# OpenSoundPhoton.net
KiCad netlist of a schematic drawn in EAGLE
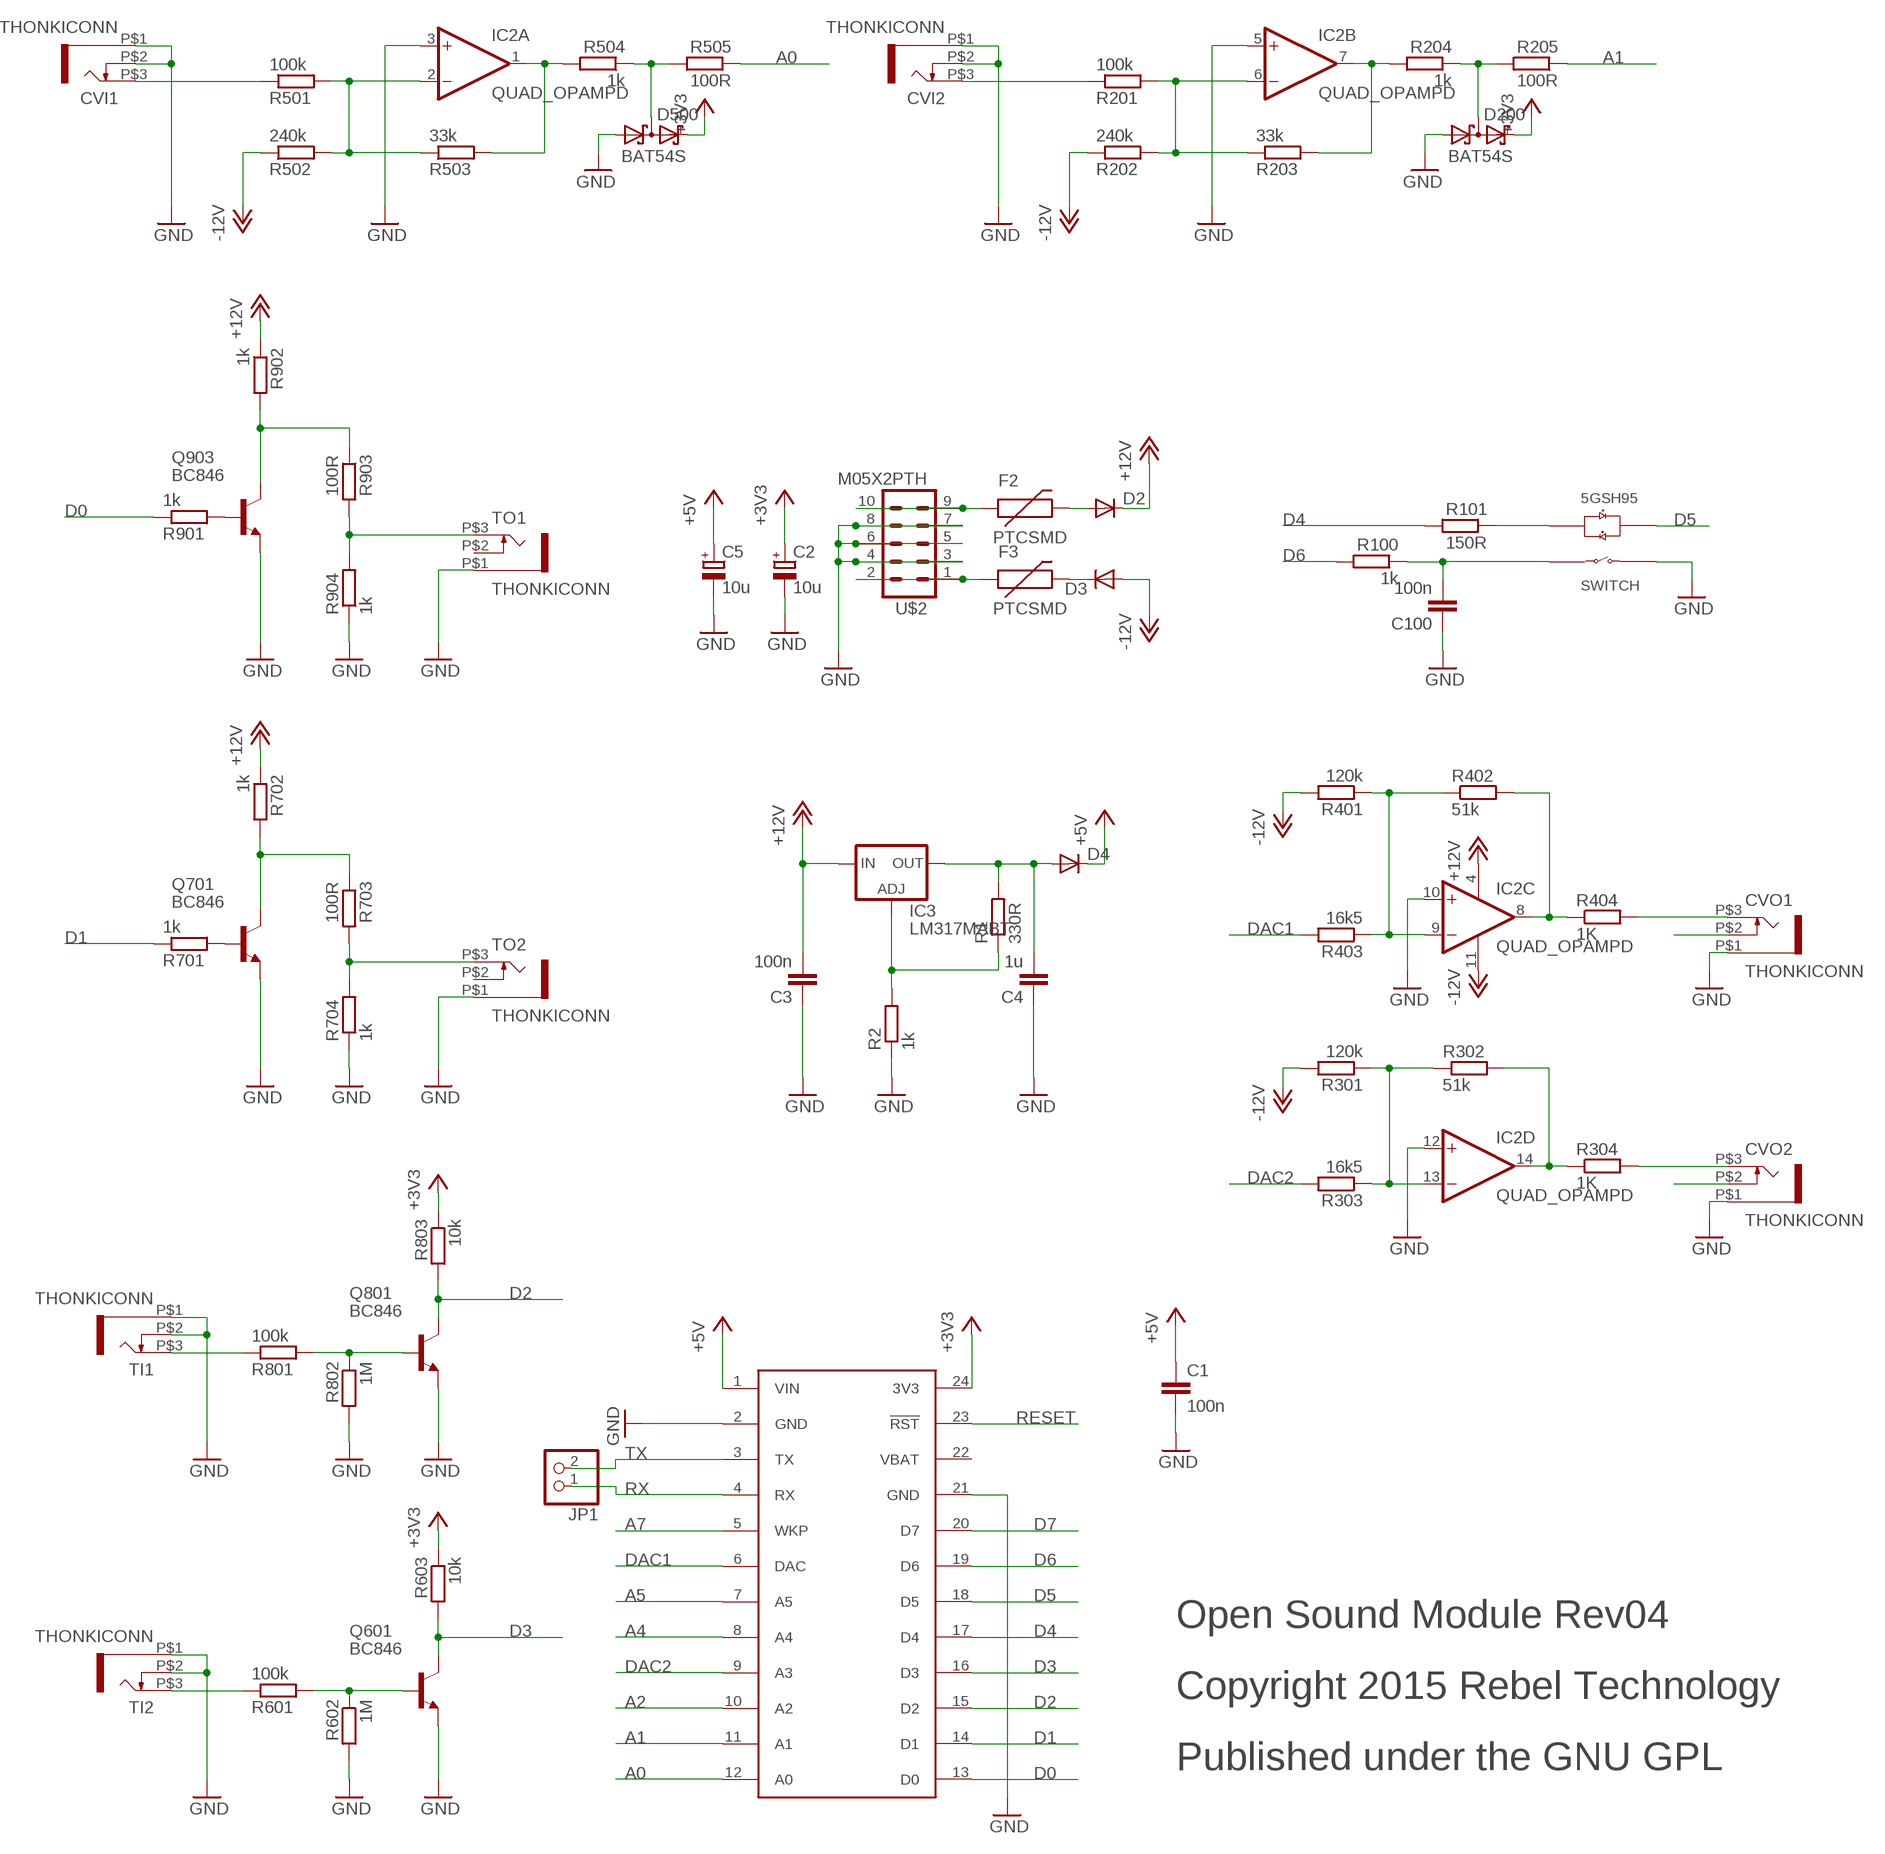
[diagram p0: schematic, sheet 1]

(export (version "E")
  (design (tool "Eeschema 10.0.6"))
  (components
    (comp (ref "C1")
      (value "100n")
      (footprint "eagle-import:C0603")
      (libsource (lib "eagle-import") (part "resistor_C-EUC0603"))
    )
    (comp (ref "C2")
      (value "10u")
      (footprint "eagle-import:SANYO-OSCON_SMD_A5")
      (libsource (lib "eagle-import") (part "CPOL-EUSANYO_SMD_A5"))
    )
    (comp (ref "C3")
      (value "100n")
      (footprint "eagle-import:C0603")
      (libsource (lib "eagle-import") (part "C-EUC0603"))
    )
    (comp (ref "C4")
      (value "1u")
      (footprint "eagle-import:C0603")
      (libsource (lib "eagle-import") (part "C-EUC0603"))
    )
    (comp (ref "C5")
      (value "10u")
      (footprint "eagle-import:SANYO-OSCON_SMD_A5")
      (libsource (lib "eagle-import") (part "CPOL-EUSANYO_SMD_A5"))
    )
    (comp (ref "C100")
      (value "100n")
      (footprint "eagle-import:C0603")
      (libsource (lib "eagle-import") (part "C-EUC0603"))
    )
    (comp (ref "CVI1")
      (value "THONKICONN")
      (footprint "eagle-import:THONKICONN")
      (libsource (lib "eagle-import") (part "THONKICONN"))
    )
    (comp (ref "CVI2")
      (value "THONKICONN")
      (footprint "eagle-import:THONKICONN")
      (libsource (lib "eagle-import") (part "THONKICONN"))
    )
    (comp (ref "CVO1")
      (value "THONKICONN")
      (footprint "eagle-import:THONKICONN")
      (libsource (lib "eagle-import") (part "THONKICONN"))
    )
    (comp (ref "CVO2")
      (value "THONKICONN")
      (footprint "eagle-import:THONKICONN")
      (libsource (lib "eagle-import") (part "THONKICONN"))
    )
    (comp (ref "D2")
      (value "DIODESMA")
      (footprint "eagle-import:SMA-DIODE")
      (libsource (lib "eagle-import") (part "DIODESMA"))
    )
    (comp (ref "D3")
      (value "DIODESMA")
      (footprint "eagle-import:SMA-DIODE")
      (libsource (lib "eagle-import") (part "DIODESMA"))
    )
    (comp (ref "D4")
      (value "DIODESMA")
      (footprint "eagle-import:SMA-DIODE")
      (libsource (lib "eagle-import") (part "DIODESMA"))
    )
    (comp (ref "D200")
      (value "BAT54S")
      (footprint "eagle-import:SOT23")
      (libsource (lib "eagle-import") (part "BAT54S"))
    )
    (comp (ref "D500")
      (value "BAT54S")
      (footprint "eagle-import:SOT23")
      (libsource (lib "eagle-import") (part "BAT54S"))
    )
    (comp (ref "F2")
      (value "PTCSMD")
      (footprint "eagle-import:PTC-1206")
      (libsource (lib "eagle-import") (part "PTCSMD"))
    )
    (comp (ref "F3")
      (value "PTCSMD")
      (footprint "eagle-import:PTC-1206")
      (libsource (lib "eagle-import") (part "PTCSMD"))
    )
    (comp (ref "IC2")
      (value "QUAD_OPAMPD")
      (footprint "eagle-import:SO14")
      (libsource (lib "eagle-import") (part "QUAD_OPAMPD"))
    )
    (comp (ref "IC3")
      (value "LM317MABT")
      (footprint "eagle-import:TO220L1")
      (libsource (lib "eagle-import") (part "LM317?MABT"))
    )
    (comp (ref "JP1")
      (value "PINHD-1X2")
      (footprint "eagle-import:1X02")
      (libsource (lib "eagle-import") (part "PINHD-1X2"))
    )
    (comp (ref "Q601")
      (value "BC846")
      (footprint "eagle-import:SOT23")
      (libsource (lib "eagle-import") (part "BC846"))
    )
    (comp (ref "Q701")
      (value "BC846")
      (footprint "eagle-import:SOT23")
      (libsource (lib "eagle-import") (part "BC846"))
    )
    (comp (ref "Q801")
      (value "BC846")
      (footprint "eagle-import:SOT23")
      (libsource (lib "eagle-import") (part "BC846"))
    )
    (comp (ref "Q903")
      (value "BC846")
      (footprint "eagle-import:SOT23")
      (libsource (lib "eagle-import") (part "BC846"))
    )
    (comp (ref "R1")
      (value "330R")
      (footprint "eagle-import:0603")
      (libsource (lib "eagle-import") (part "R-EU_0603"))
    )
    (comp (ref "R2")
      (value "1k")
      (footprint "eagle-import:0603")
      (libsource (lib "eagle-import") (part "R-EU_0603"))
    )
    (comp (ref "R100")
      (value "1k")
      (footprint "eagle-import:0603")
      (libsource (lib "eagle-import") (part "R-EU_0603"))
    )
    (comp (ref "R101")
      (value "150R")
      (footprint "eagle-import:0603")
      (libsource (lib "eagle-import") (part "R-EU_0603"))
    )
    (comp (ref "R201")
      (value "100k")
      (footprint "eagle-import:0603")
      (libsource (lib "eagle-import") (part "R-EU_0603"))
    )
    (comp (ref "R202")
      (value "240k")
      (footprint "eagle-import:0603")
      (libsource (lib "eagle-import") (part "R-EU_0603"))
    )
    (comp (ref "R203")
      (value "33k")
      (footprint "eagle-import:0603")
      (libsource (lib "eagle-import") (part "R-EU_0603"))
    )
    (comp (ref "R204")
      (value "1k")
      (footprint "eagle-import:0603")
      (libsource (lib "eagle-import") (part "R-EU_0603"))
    )
    (comp (ref "R205")
      (value "100R")
      (footprint "eagle-import:0603")
      (libsource (lib "eagle-import") (part "R-EU_0603"))
    )
    (comp (ref "R301")
      (value "120k")
      (footprint "eagle-import:0603")
      (libsource (lib "eagle-import") (part "R-EU_0603"))
    )
    (comp (ref "R302")
      (value "51k")
      (footprint "eagle-import:0603")
      (libsource (lib "eagle-import") (part "R-EU_0603"))
    )
    (comp (ref "R303")
      (value "16k5")
      (footprint "eagle-import:0603")
      (libsource (lib "eagle-import") (part "R-EU_0603"))
    )
    (comp (ref "R304")
      (value "1K")
      (footprint "eagle-import:0603")
      (libsource (lib "eagle-import") (part "R-EU_0603"))
    )
    (comp (ref "R401")
      (value "120k")
      (footprint "eagle-import:0603")
      (libsource (lib "eagle-import") (part "R-EU_0603"))
    )
    (comp (ref "R402")
      (value "51k")
      (footprint "eagle-import:0603")
      (libsource (lib "eagle-import") (part "R-EU_0603"))
    )
    (comp (ref "R403")
      (value "16k5")
      (footprint "eagle-import:0603")
      (libsource (lib "eagle-import") (part "R-EU_0603"))
    )
    (comp (ref "R404")
      (value "1K")
      (footprint "eagle-import:0603")
      (libsource (lib "eagle-import") (part "R-EU_0603"))
    )
    (comp (ref "R501")
      (value "100k")
      (footprint "eagle-import:0603")
      (libsource (lib "eagle-import") (part "R-EU_0603"))
    )
    (comp (ref "R502")
      (value "240k")
      (footprint "eagle-import:0603")
      (libsource (lib "eagle-import") (part "R-EU_0603"))
    )
    (comp (ref "R503")
      (value "33k")
      (footprint "eagle-import:0603")
      (libsource (lib "eagle-import") (part "R-EU_0603"))
    )
    (comp (ref "R504")
      (value "1k")
      (footprint "eagle-import:0603")
      (libsource (lib "eagle-import") (part "R-EU_0603"))
    )
    (comp (ref "R505")
      (value "100R")
      (footprint "eagle-import:0603")
      (libsource (lib "eagle-import") (part "R-EU_0603"))
    )
    (comp (ref "R601")
      (value "100k")
      (footprint "eagle-import:0603")
      (libsource (lib "eagle-import") (part "R-EU_0603"))
    )
    (comp (ref "R602")
      (value "1M")
      (footprint "eagle-import:0603")
      (libsource (lib "eagle-import") (part "R-EU_0603"))
    )
    (comp (ref "R603")
      (value "10k")
      (footprint "eagle-import:0603")
      (libsource (lib "eagle-import") (part "R-EU_0603"))
    )
    (comp (ref "R701")
      (value "1k")
      (footprint "eagle-import:0603")
      (libsource (lib "eagle-import") (part "R-EU_0603"))
    )
    (comp (ref "R702")
      (value "1k")
      (footprint "eagle-import:0603")
      (libsource (lib "eagle-import") (part "R-EU_0603"))
    )
    (comp (ref "R703")
      (value "100R")
      (footprint "eagle-import:0603")
      (libsource (lib "eagle-import") (part "R-EU_0603"))
    )
    (comp (ref "R704")
      (value "1k")
      (footprint "eagle-import:0603")
      (libsource (lib "eagle-import") (part "R-EU_0603"))
    )
    (comp (ref "R801")
      (value "100k")
      (footprint "eagle-import:0603")
      (libsource (lib "eagle-import") (part "R-EU_0603"))
    )
    (comp (ref "R802")
      (value "1M")
      (footprint "eagle-import:0603")
      (libsource (lib "eagle-import") (part "R-EU_0603"))
    )
    (comp (ref "R803")
      (value "10k")
      (footprint "eagle-import:0603")
      (libsource (lib "eagle-import") (part "R-EU_0603"))
    )
    (comp (ref "R901")
      (value "1k")
      (footprint "eagle-import:0603")
      (libsource (lib "eagle-import") (part "R-EU_0603"))
    )
    (comp (ref "R902")
      (value "1k")
      (footprint "eagle-import:0603")
      (libsource (lib "eagle-import") (part "R-EU_0603"))
    )
    (comp (ref "R903")
      (value "100R")
      (footprint "eagle-import:0603")
      (libsource (lib "eagle-import") (part "R-EU_0603"))
    )
    (comp (ref "R904")
      (value "1k")
      (footprint "eagle-import:0603")
      (libsource (lib "eagle-import") (part "R-EU_0603"))
    )
    (comp (ref "SPARK")
      (value "SPARK_CORE")
      (footprint "eagle-import:SPARK_CORE")
      (libsource (lib "eagle-import") (part "SPARK_CORECORE"))
    )
    (comp (ref "TI1")
      (value "THONKICONN")
      (footprint "eagle-import:THONKICONN")
      (libsource (lib "eagle-import") (part "THONKICONN"))
    )
    (comp (ref "TI2")
      (value "THONKICONN")
      (footprint "eagle-import:THONKICONN")
      (libsource (lib "eagle-import") (part "THONKICONN"))
    )
    (comp (ref "TO1")
      (value "THONKICONN")
      (footprint "eagle-import:THONKICONN")
      (libsource (lib "eagle-import") (part "THONKICONN"))
    )
    (comp (ref "TO2")
      (value "THONKICONN")
      (footprint "eagle-import:THONKICONN")
      (libsource (lib "eagle-import") (part "THONKICONN"))
    )
    (comp (ref "U$1")
      (value "5GTH9")
      (footprint "eagle-import:5GTH9")
      (libsource (lib "eagle-import") (part "5GTH9"))
    )
    (comp (ref "U$2")
      (value "M05X2PTH")
      (footprint "eagle-import:AVR_ICSP")
      (libsource (lib "eagle-import") (part "M05X2PTH"))
    )
  )
  (nets
    (net (code "1") (name "+3V3") (class "Default")
      (node (ref "C2") (pin "+") (pinfunction "+_+") (pintype "passive"))
      (node (ref "D200") (pin "2") (pinfunction "C2_2") (pintype "passive"))
      (node (ref "D500") (pin "2") (pinfunction "C2_2") (pintype "passive"))
      (node (ref "R603") (pin "1") (pinfunction "1_1") (pintype "passive"))
      (node (ref "R803") (pin "1") (pinfunction "1_1") (pintype "passive"))
      (node (ref "SPARK") (pin "24") (pinfunction "3V3_24") (pintype "power_in"))
    )
    (net (code "2") (name "+5V") (class "Default")
      (node (ref "C1") (pin "1") (pinfunction "1_1") (pintype "passive"))
      (node (ref "C5") (pin "+") (pinfunction "+_+") (pintype "passive"))
      (node (ref "D4") (pin "C") (pinfunction "C_C") (pintype "passive"))
      (node (ref "SPARK") (pin "1") (pinfunction "VIN_1") (pintype "power_in"))
    )
    (net (code "3") (name "+12V") (class "Default")
      (node (ref "C3") (pin "2") (pinfunction "2_2") (pintype "passive"))
      (node (ref "D2") (pin "C") (pinfunction "C_C") (pintype "passive"))
      (node (ref "IC2") (pin "4") (pinfunction "V+_4") (pintype "power_in"))
      (node (ref "IC3") (pin "3") (pinfunction "IN_3") (pintype "input"))
      (node (ref "R702") (pin "1") (pinfunction "1_1") (pintype "passive"))
      (node (ref "R902") (pin "1") (pinfunction "1_1") (pintype "passive"))
    )
    (net (code "4") (name "-12V") (class "Default")
      (node (ref "D3") (pin "A") (pinfunction "A_A") (pintype "passive"))
      (node (ref "IC2") (pin "11") (pinfunction "V-_11") (pintype "power_in"))
      (node (ref "R202") (pin "1") (pinfunction "1_1") (pintype "passive"))
      (node (ref "R301") (pin "2") (pinfunction "2_2") (pintype "passive"))
      (node (ref "R401") (pin "2") (pinfunction "2_2") (pintype "passive"))
      (node (ref "R502") (pin "1") (pinfunction "1_1") (pintype "passive"))
    )
    (net (code "5") (name "/A0") (class "Default")
      (node (ref "R505") (pin "1") (pinfunction "1_1") (pintype "passive"))
      (node (ref "SPARK") (pin "12") (pinfunction "A0_12") (pintype "bidirectional"))
    )
    (net (code "6") (name "/A1") (class "Default")
      (node (ref "R205") (pin "1") (pinfunction "1_1") (pintype "passive"))
      (node (ref "SPARK") (pin "11") (pinfunction "A1_11") (pintype "bidirectional"))
    )
    (net (code "7") (name "/A2") (class "Default")
      (node (ref "SPARK") (pin "10") (pinfunction "A2_10") (pintype "bidirectional"))
    )
    (net (code "8") (name "/A4") (class "Default")
      (node (ref "SPARK") (pin "8") (pinfunction "A4_8") (pintype "bidirectional"))
    )
    (net (code "9") (name "/A5") (class "Default")
      (node (ref "SPARK") (pin "7") (pinfunction "A5_7") (pintype "bidirectional"))
    )
    (net (code "10") (name "/A7") (class "Default")
      (node (ref "SPARK") (pin "5") (pinfunction "WKP_5") (pintype "bidirectional"))
    )
    (net (code "11") (name "/D0") (class "Default")
      (node (ref "R901") (pin "1") (pinfunction "1_1") (pintype "passive"))
      (node (ref "SPARK") (pin "13") (pinfunction "D0_13") (pintype "bidirectional"))
    )
    (net (code "12") (name "/D1") (class "Default")
      (node (ref "R701") (pin "1") (pinfunction "1_1") (pintype "passive"))
      (node (ref "SPARK") (pin "14") (pinfunction "D1_14") (pintype "bidirectional"))
    )
    (net (code "13") (name "/D2") (class "Default")
      (node (ref "Q801") (pin "3") (pinfunction "C_3") (pintype "passive"))
      (node (ref "R803") (pin "2") (pinfunction "2_2") (pintype "passive"))
      (node (ref "SPARK") (pin "15") (pinfunction "D2_15") (pintype "bidirectional"))
    )
    (net (code "14") (name "/D3") (class "Default")
      (node (ref "Q601") (pin "3") (pinfunction "C_3") (pintype "passive"))
      (node (ref "R603") (pin "2") (pinfunction "2_2") (pintype "passive"))
      (node (ref "SPARK") (pin "16") (pinfunction "D3_16") (pintype "bidirectional"))
    )
    (net (code "15") (name "/D4") (class "Default")
      (node (ref "R101") (pin "2") (pinfunction "2_2") (pintype "passive"))
      (node (ref "SPARK") (pin "17") (pinfunction "D4_17") (pintype "bidirectional"))
    )
    (net (code "16") (name "/D5") (class "Default")
      (node (ref "SPARK") (pin "18") (pinfunction "D5_18") (pintype "bidirectional"))
      (node (ref "U$1") (pin "+3") (pinfunction "LED_R+_+3") (pintype "input"))
    )
    (net (code "17") (name "/D6") (class "Default")
      (node (ref "R100") (pin "2") (pinfunction "2_2") (pintype "passive"))
      (node (ref "SPARK") (pin "19") (pinfunction "D6_19") (pintype "bidirectional"))
    )
    (net (code "18") (name "/D7") (class "Default")
      (node (ref "SPARK") (pin "20") (pinfunction "D7_20") (pintype "bidirectional"))
    )
    (net (code "19") (name "/DAC1") (class "Default")
      (node (ref "R403") (pin "2") (pinfunction "2_2") (pintype "passive"))
      (node (ref "SPARK") (pin "6") (pinfunction "DAC_6") (pintype "bidirectional"))
    )
    (net (code "20") (name "/DAC2") (class "Default")
      (node (ref "R303") (pin "2") (pinfunction "2_2") (pintype "passive"))
      (node (ref "SPARK") (pin "9") (pinfunction "A3_9") (pintype "bidirectional"))
    )
    (net (code "21") (name "/RESET") (class "Default")
      (node (ref "SPARK") (pin "23") (pinfunction "~{RST}_23") (pintype "bidirectional"))
    )
    (net (code "22") (name "/RX") (class "Default")
      (node (ref "JP1") (pin "1") (pinfunction "1_1") (pintype "passive"))
      (node (ref "SPARK") (pin "4") (pinfunction "RX_4") (pintype "bidirectional"))
    )
    (net (code "23") (name "/TX") (class "Default")
      (node (ref "JP1") (pin "2") (pinfunction "2_2") (pintype "passive"))
      (node (ref "SPARK") (pin "3") (pinfunction "TX_3") (pintype "bidirectional"))
    )
    (net (code "24") (name "/VBAT") (class "Default")
      (node (ref "SPARK") (pin "22") (pinfunction "VBAT_22") (pintype "power_in"))
    )
    (net (code "25") (name "GND") (class "Default")
      (node (ref "C1") (pin "2") (pinfunction "2_2") (pintype "passive"))
      (node (ref "C100") (pin "1") (pinfunction "1_1") (pintype "passive"))
      (node (ref "C2") (pin "-") (pinfunction "-_-") (pintype "passive"))
      (node (ref "C3") (pin "1") (pinfunction "1_1") (pintype "passive"))
      (node (ref "C4") (pin "1") (pinfunction "1_1") (pintype "passive"))
      (node (ref "C5") (pin "-") (pinfunction "-_-") (pintype "passive"))
      (node (ref "CVI1") (pin "P$1") (pinfunction "5_P$1") (pintype "passive"))
      (node (ref "CVI1") (pin "P$2") (pinfunction "4_P$2") (pintype "passive"))
      (node (ref "CVI2") (pin "P$1") (pinfunction "5_P$1") (pintype "passive"))
      (node (ref "CVI2") (pin "P$2") (pinfunction "4_P$2") (pintype "passive"))
      (node (ref "CVO1") (pin "P$1") (pinfunction "5_P$1") (pintype "passive"))
      (node (ref "CVO2") (pin "P$1") (pinfunction "5_P$1") (pintype "passive"))
      (node (ref "D200") (pin "1") (pinfunction "A1_1") (pintype "passive"))
      (node (ref "D500") (pin "1") (pinfunction "A1_1") (pintype "passive"))
      (node (ref "IC2") (pin "10") (pinfunction "+IN_10") (pintype "input"))
      (node (ref "IC2") (pin "12") (pinfunction "+IN_12") (pintype "input"))
      (node (ref "IC2") (pin "3") (pinfunction "+IN_3") (pintype "input"))
      (node (ref "IC2") (pin "5") (pinfunction "+IN_5") (pintype "input"))
      (node (ref "Q601") (pin "2") (pinfunction "E_2") (pintype "passive"))
      (node (ref "Q701") (pin "2") (pinfunction "E_2") (pintype "passive"))
      (node (ref "Q801") (pin "2") (pinfunction "E_2") (pintype "passive"))
      (node (ref "Q903") (pin "2") (pinfunction "E_2") (pintype "passive"))
      (node (ref "R2") (pin "1") (pinfunction "1_1") (pintype "passive"))
      (node (ref "R602") (pin "2") (pinfunction "2_2") (pintype "passive"))
      (node (ref "R704") (pin "1") (pinfunction "1_1") (pintype "passive"))
      (node (ref "R802") (pin "2") (pinfunction "2_2") (pintype "passive"))
      (node (ref "R904") (pin "1") (pinfunction "1_1") (pintype "passive"))
      (node (ref "SPARK") (pin "2") (pinfunction "GND_2") (pintype "power_in"))
      (node (ref "SPARK") (pin "21") (pinfunction "GND_21") (pintype "power_in"))
      (node (ref "TI1") (pin "P$1") (pinfunction "5_P$1") (pintype "passive"))
      (node (ref "TI1") (pin "P$2") (pinfunction "4_P$2") (pintype "passive"))
      (node (ref "TI2") (pin "P$1") (pinfunction "5_P$1") (pintype "passive"))
      (node (ref "TI2") (pin "P$2") (pinfunction "4_P$2") (pintype "passive"))
      (node (ref "TO1") (pin "P$1") (pinfunction "5_P$1") (pintype "passive"))
      (node (ref "TO2") (pin "P$1") (pinfunction "5_P$1") (pintype "passive"))
      (node (ref "U$1") (pin "1") (pinfunction "SWITCH_B_1") (pintype "power_in"))
      (node (ref "U$2") (pin "3") (pinfunction "3_3") (pintype "passive"))
      (node (ref "U$2") (pin "4") (pinfunction "4_4") (pintype "passive"))
      (node (ref "U$2") (pin "5") (pinfunction "5_5") (pintype "passive"))
      (node (ref "U$2") (pin "6") (pinfunction "6_6") (pintype "passive"))
      (node (ref "U$2") (pin "7") (pinfunction "7_7") (pintype "passive"))
      (node (ref "U$2") (pin "8") (pinfunction "8_8") (pintype "passive"))
    )
    (net (code "26") (name "Net-(CVI1-3)") (class "Default")
      (node (ref "CVI1") (pin "P$3") (pinfunction "3_P$3") (pintype "passive"))
      (node (ref "R501") (pin "1") (pinfunction "1_1") (pintype "passive"))
    )
    (net (code "27") (name "Net-(CVI2-3)") (class "Default")
      (node (ref "CVI2") (pin "P$3") (pinfunction "3_P$3") (pintype "passive"))
      (node (ref "R201") (pin "1") (pinfunction "1_1") (pintype "passive"))
    )
    (net (code "28") (name "Net-(CVO1-3)") (class "Default")
      (node (ref "CVO1") (pin "P$3") (pinfunction "3_P$3") (pintype "passive"))
      (node (ref "R404") (pin "2") (pinfunction "2_2") (pintype "passive"))
    )
    (net (code "29") (name "Net-(CVO2-3)") (class "Default")
      (node (ref "CVO2") (pin "P$3") (pinfunction "3_P$3") (pintype "passive"))
      (node (ref "R304") (pin "2") (pinfunction "2_2") (pintype "passive"))
    )
    (net (code "30") (name "Net-(D2-PadA)") (class "Default")
      (node (ref "D2") (pin "A") (pinfunction "A_A") (pintype "passive"))
      (node (ref "F2") (pin "2") (pinfunction "2_2") (pintype "bidirectional"))
    )
    (net (code "31") (name "Net-(D3-PadC)") (class "Default")
      (node (ref "D3") (pin "C") (pinfunction "C_C") (pintype "passive"))
      (node (ref "F3") (pin "2") (pinfunction "2_2") (pintype "bidirectional"))
    )
    (net (code "32") (name "Net-(D200-C1A2)") (class "Default")
      (node (ref "D200") (pin "3") (pinfunction "C1A2_3") (pintype "passive"))
      (node (ref "R204") (pin "1") (pinfunction "1_1") (pintype "passive"))
      (node (ref "R205") (pin "2") (pinfunction "2_2") (pintype "passive"))
    )
    (net (code "33") (name "Net-(D500-C1A2)") (class "Default")
      (node (ref "D500") (pin "3") (pinfunction "C1A2_3") (pintype "passive"))
      (node (ref "R504") (pin "1") (pinfunction "1_1") (pintype "passive"))
      (node (ref "R505") (pin "2") (pinfunction "2_2") (pintype "passive"))
    )
    (net (code "34") (name "Net-(F2-Pad1)") (class "Default")
      (node (ref "F2") (pin "1") (pinfunction "1_1") (pintype "bidirectional"))
      (node (ref "U$2") (pin "10") (pinfunction "10_10") (pintype "passive"))
      (node (ref "U$2") (pin "9") (pinfunction "9_9") (pintype "passive"))
    )
    (net (code "35") (name "Net-(F3-Pad1)") (class "Default")
      (node (ref "F3") (pin "1") (pinfunction "1_1") (pintype "bidirectional"))
      (node (ref "U$2") (pin "1") (pinfunction "1_1") (pintype "passive"))
      (node (ref "U$2") (pin "2") (pinfunction "2_2") (pintype "passive"))
    )
    (net (code "36") (name "Net-(IC2A--IN)") (class "Default")
      (node (ref "IC2") (pin "2") (pinfunction "-IN_2") (pintype "input"))
      (node (ref "R501") (pin "2") (pinfunction "2_2") (pintype "passive"))
      (node (ref "R502") (pin "2") (pinfunction "2_2") (pintype "passive"))
      (node (ref "R503") (pin "1") (pinfunction "1_1") (pintype "passive"))
    )
    (net (code "37") (name "Net-(IC2A-OUT)") (class "Default")
      (node (ref "IC2") (pin "1") (pinfunction "OUT_1") (pintype "output"))
      (node (ref "R503") (pin "2") (pinfunction "2_2") (pintype "passive"))
      (node (ref "R504") (pin "2") (pinfunction "2_2") (pintype "passive"))
    )
    (net (code "38") (name "Net-(IC2B--IN)") (class "Default")
      (node (ref "IC2") (pin "6") (pinfunction "-IN_6") (pintype "input"))
      (node (ref "R201") (pin "2") (pinfunction "2_2") (pintype "passive"))
      (node (ref "R202") (pin "2") (pinfunction "2_2") (pintype "passive"))
      (node (ref "R203") (pin "1") (pinfunction "1_1") (pintype "passive"))
    )
    (net (code "39") (name "Net-(IC2B-OUT)") (class "Default")
      (node (ref "IC2") (pin "7") (pinfunction "OUT_7") (pintype "output"))
      (node (ref "R203") (pin "2") (pinfunction "2_2") (pintype "passive"))
      (node (ref "R204") (pin "2") (pinfunction "2_2") (pintype "passive"))
    )
    (net (code "40") (name "Net-(IC2C--IN)") (class "Default")
      (node (ref "IC2") (pin "9") (pinfunction "-IN_9") (pintype "input"))
      (node (ref "R401") (pin "1") (pinfunction "1_1") (pintype "passive"))
      (node (ref "R402") (pin "1") (pinfunction "1_1") (pintype "passive"))
      (node (ref "R403") (pin "1") (pinfunction "1_1") (pintype "passive"))
    )
    (net (code "41") (name "Net-(IC2C-OUT)") (class "Default")
      (node (ref "IC2") (pin "8") (pinfunction "OUT_8") (pintype "output"))
      (node (ref "R402") (pin "2") (pinfunction "2_2") (pintype "passive"))
      (node (ref "R404") (pin "1") (pinfunction "1_1") (pintype "passive"))
    )
    (net (code "42") (name "Net-(IC2D--IN)") (class "Default")
      (node (ref "IC2") (pin "13") (pinfunction "-IN_13") (pintype "input"))
      (node (ref "R301") (pin "1") (pinfunction "1_1") (pintype "passive"))
      (node (ref "R302") (pin "1") (pinfunction "1_1") (pintype "passive"))
      (node (ref "R303") (pin "1") (pinfunction "1_1") (pintype "passive"))
    )
    (net (code "43") (name "Net-(IC2D-OUT)") (class "Default")
      (node (ref "IC2") (pin "14") (pinfunction "OUT_14") (pintype "output"))
      (node (ref "R302") (pin "2") (pinfunction "2_2") (pintype "passive"))
      (node (ref "R304") (pin "1") (pinfunction "1_1") (pintype "passive"))
    )
    (net (code "44") (name "Net-(IC3-ADJ)") (class "Default")
      (node (ref "IC3") (pin "1") (pinfunction "ADJ_1") (pintype "input"))
      (node (ref "R1") (pin "1") (pinfunction "1_1") (pintype "passive"))
      (node (ref "R2") (pin "2") (pinfunction "2_2") (pintype "passive"))
    )
    (net (code "45") (name "Net-(IC3-OUT)") (class "Default")
      (node (ref "C4") (pin "2") (pinfunction "2_2") (pintype "passive"))
      (node (ref "D4") (pin "A") (pinfunction "A_A") (pintype "passive"))
      (node (ref "IC3") (pin "2") (pinfunction "OUT_2") (pintype "passive"))
      (node (ref "R1") (pin "2") (pinfunction "2_2") (pintype "passive"))
    )
    (net (code "46") (name "Net-(Q601-B)") (class "Default")
      (node (ref "Q601") (pin "1") (pinfunction "B_1") (pintype "passive"))
      (node (ref "R601") (pin "2") (pinfunction "2_2") (pintype "passive"))
      (node (ref "R602") (pin "1") (pinfunction "1_1") (pintype "passive"))
    )
    (net (code "47") (name "Net-(Q701-B)") (class "Default")
      (node (ref "Q701") (pin "1") (pinfunction "B_1") (pintype "passive"))
      (node (ref "R701") (pin "2") (pinfunction "2_2") (pintype "passive"))
    )
    (net (code "48") (name "Net-(Q701-C)") (class "Default")
      (node (ref "Q701") (pin "3") (pinfunction "C_3") (pintype "passive"))
      (node (ref "R702") (pin "2") (pinfunction "2_2") (pintype "passive"))
      (node (ref "R703") (pin "1") (pinfunction "1_1") (pintype "passive"))
    )
    (net (code "49") (name "Net-(Q801-B)") (class "Default")
      (node (ref "Q801") (pin "1") (pinfunction "B_1") (pintype "passive"))
      (node (ref "R801") (pin "2") (pinfunction "2_2") (pintype "passive"))
      (node (ref "R802") (pin "1") (pinfunction "1_1") (pintype "passive"))
    )
    (net (code "50") (name "Net-(Q903-B)") (class "Default")
      (node (ref "Q903") (pin "1") (pinfunction "B_1") (pintype "passive"))
      (node (ref "R901") (pin "2") (pinfunction "2_2") (pintype "passive"))
    )
    (net (code "51") (name "Net-(Q903-C)") (class "Default")
      (node (ref "Q903") (pin "3") (pinfunction "C_3") (pintype "passive"))
      (node (ref "R902") (pin "2") (pinfunction "2_2") (pintype "passive"))
      (node (ref "R903") (pin "1") (pinfunction "1_1") (pintype "passive"))
    )
    (net (code "52") (name "Net-(TI1-3)") (class "Default")
      (node (ref "R801") (pin "1") (pinfunction "1_1") (pintype "passive"))
      (node (ref "TI1") (pin "P$3") (pinfunction "3_P$3") (pintype "passive"))
    )
    (net (code "53") (name "Net-(TI2-3)") (class "Default")
      (node (ref "R601") (pin "1") (pinfunction "1_1") (pintype "passive"))
      (node (ref "TI2") (pin "P$3") (pinfunction "3_P$3") (pintype "passive"))
    )
    (net (code "54") (name "Net-(TO1-3)") (class "Default")
      (node (ref "R903") (pin "2") (pinfunction "2_2") (pintype "passive"))
      (node (ref "R904") (pin "2") (pinfunction "2_2") (pintype "passive"))
      (node (ref "TO1") (pin "P$3") (pinfunction "3_P$3") (pintype "passive"))
    )
    (net (code "55") (name "Net-(TO2-3)") (class "Default")
      (node (ref "R703") (pin "2") (pinfunction "2_2") (pintype "passive"))
      (node (ref "R704") (pin "2") (pinfunction "2_2") (pintype "passive"))
      (node (ref "TO2") (pin "P$3") (pinfunction "3_P$3") (pintype "passive"))
    )
    (net (code "56") (name "Net-(U$1-LED_G+)") (class "Default")
      (node (ref "R101") (pin "1") (pinfunction "1_1") (pintype "passive"))
      (node (ref "U$1") (pin "-2") (pinfunction "LED_G+_-2") (pintype "input"))
    )
    (net (code "57") (name "Net-(U$1-SWITCH_A)") (class "Default")
      (node (ref "C100") (pin "2") (pinfunction "2_2") (pintype "passive"))
      (node (ref "R100") (pin "1") (pinfunction "1_1") (pintype "passive"))
      (node (ref "U$1") (pin "4") (pinfunction "SWITCH_A_4") (pintype "power_in"))
    )
    (net (code "58") (name "unconnected-(CVO1-4-PadP$2)") (class "Default")
      (node (ref "CVO1") (pin "P$2") (pinfunction "4_P$2") (pintype "passive"))
    )
    (net (code "59") (name "unconnected-(CVO2-4-PadP$2)") (class "Default")
      (node (ref "CVO2") (pin "P$2") (pinfunction "4_P$2") (pintype "passive"))
    )
    (net (code "60") (name "unconnected-(TO1-4-PadP$2)") (class "Default")
      (node (ref "TO1") (pin "P$2") (pinfunction "4_P$2") (pintype "passive"))
    )
    (net (code "61") (name "unconnected-(TO2-4-PadP$2)") (class "Default")
      (node (ref "TO2") (pin "P$2") (pinfunction "4_P$2") (pintype "passive"))
    )
  )
)
